# working.net
KiCad netlist of a schematic drawn in EAGLE
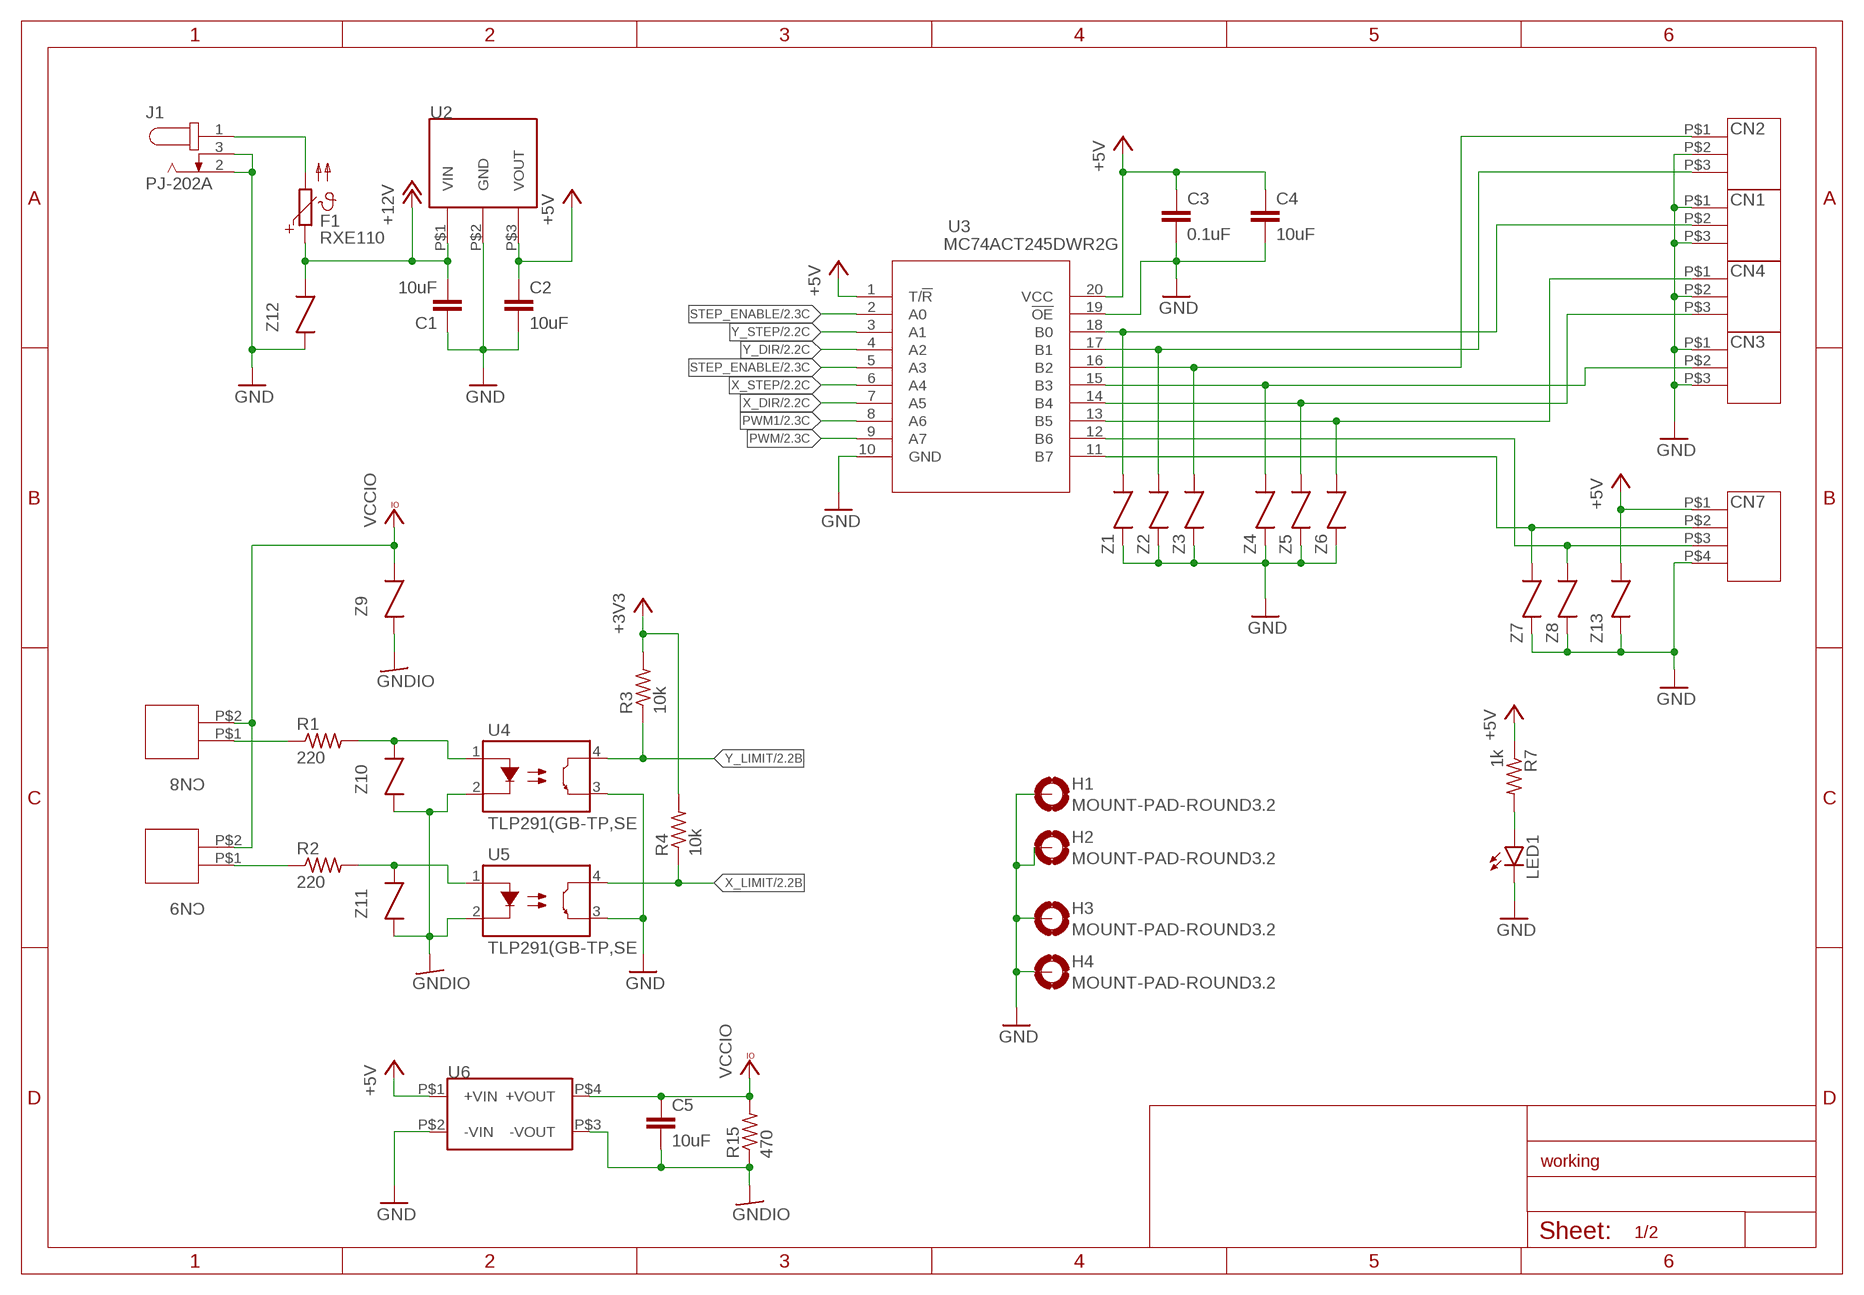
[diagram p0: schematic, sheet 1]
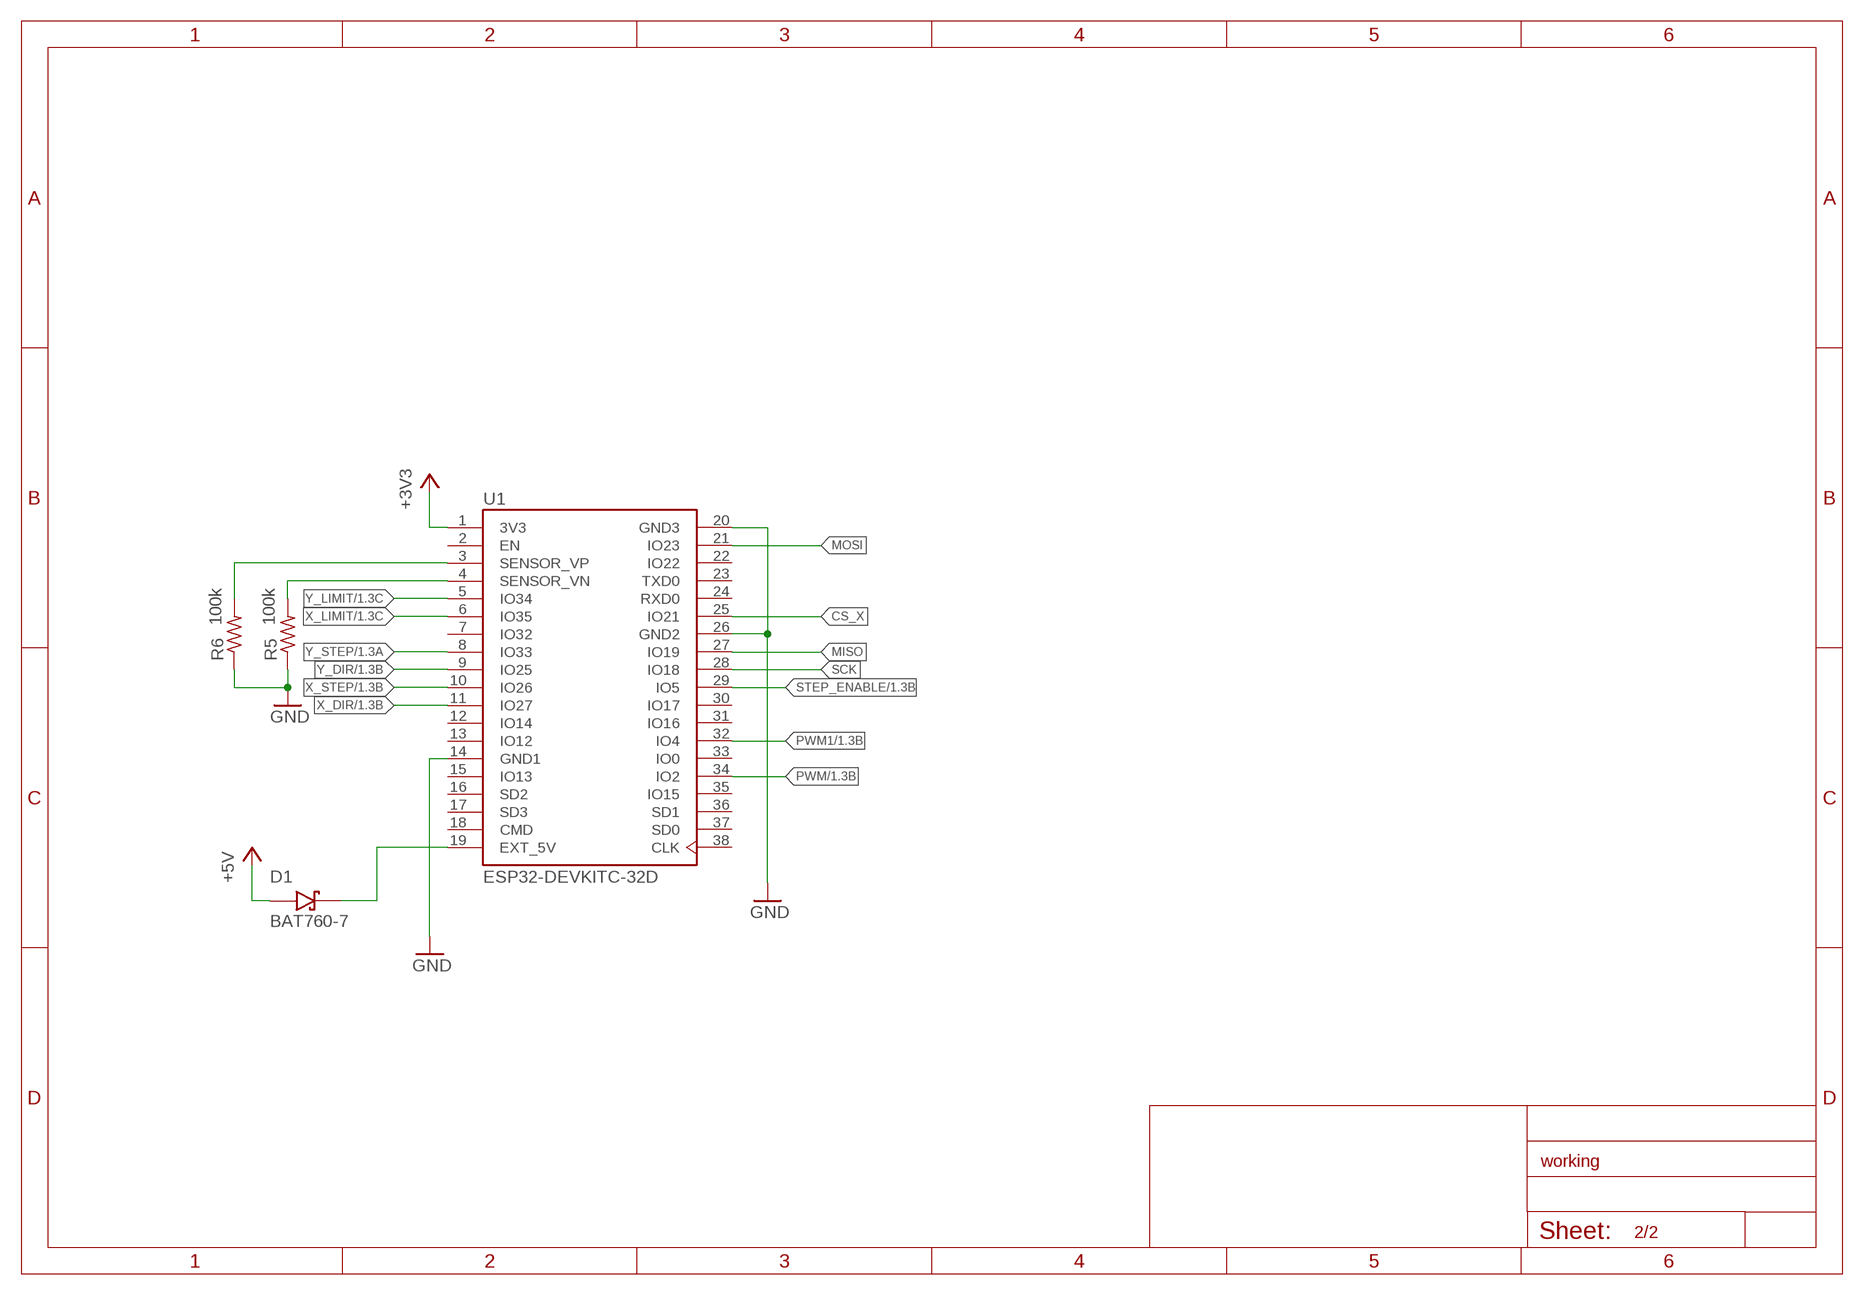
[diagram p1: schematic, sheet 2]

(export (version "E")
  (design (tool "Eeschema 10.0.6"))
  (components
    (comp (ref "C1")
      (value "10uF")
      (footprint "eagle-import:C0805")
      (libsource (lib "eagle-import") (part "C-EUC0805"))
    )
    (comp (ref "C2")
      (value "10uF")
      (footprint "eagle-import:C0805")
      (libsource (lib "eagle-import") (part "C-EUC0805"))
    )
    (comp (ref "C3")
      (value "0.1uF")
      (footprint "eagle-import:C0603")
      (libsource (lib "eagle-import") (part "C-EUC0603"))
    )
    (comp (ref "C4")
      (value "10uF")
      (footprint "eagle-import:C0805")
      (libsource (lib "eagle-import") (part "C-EUC0805"))
    )
    (comp (ref "C5")
      (value "10uF")
      (footprint "eagle-import:C0805")
      (libsource (lib "eagle-import") (part "C-EUC0805"))
    )
    (comp (ref "CN1")
      (value "ETB43034G000Z")
      (footprint "eagle-import:ETB43034G000Z")
      (libsource (lib "eagle-import") (part "ETB43034G000Z"))
    )
    (comp (ref "CN2")
      (value "ETB43034G000Z")
      (footprint "eagle-import:ETB43034G000Z")
      (libsource (lib "eagle-import") (part "ETB43034G000Z"))
    )
    (comp (ref "CN3")
      (value "ETB43034G000Z")
      (footprint "eagle-import:ETB43034G000Z")
      (libsource (lib "eagle-import") (part "ETB43034G000Z"))
    )
    (comp (ref "CN4")
      (value "ETB43034G000Z")
      (footprint "eagle-import:ETB43034G000Z")
      (libsource (lib "eagle-import") (part "ETB43034G000Z"))
    )
    (comp (ref "CN7")
      (value "ETB43044G000Z")
      (footprint "eagle-import:ETB43044G000Z")
      (libsource (lib "eagle-import") (part "ETB43044G000Z"))
    )
    (comp (ref "CN8")
      (value "ETB43024G000Z")
      (footprint "eagle-import:ETB43024G000Z")
      (libsource (lib "eagle-import") (part "ETB43024G000Z"))
    )
    (comp (ref "CN9")
      (value "ETB43024G000Z")
      (footprint "eagle-import:ETB43024G000Z")
      (libsource (lib "eagle-import") (part "ETB43024G000Z"))
    )
    (comp (ref "F1")
      (value "RXE110")
      (footprint "eagle-import:RXE110")
      (libsource (lib "eagle-import") (part "RXE110"))
    )
    (comp (ref "H1")
      (value "MOUNT-PAD-ROUND3.2")
      (footprint "eagle-import:3,2-PAD")
      (libsource (lib "eagle-import") (part "MOUNT-PAD-ROUND3.2"))
    )
    (comp (ref "H2")
      (value "MOUNT-PAD-ROUND3.2")
      (footprint "eagle-import:3,2-PAD")
      (libsource (lib "eagle-import") (part "MOUNT-PAD-ROUND3.2"))
    )
    (comp (ref "H3")
      (value "MOUNT-PAD-ROUND3.2")
      (footprint "eagle-import:3,2-PAD")
      (libsource (lib "eagle-import") (part "MOUNT-PAD-ROUND3.2"))
    )
    (comp (ref "H4")
      (value "MOUNT-PAD-ROUND3.2")
      (footprint "eagle-import:3,2-PAD")
      (libsource (lib "eagle-import") (part "MOUNT-PAD-ROUND3.2"))
    )
    (comp (ref "J1")
      (value "PJ-202A")
      (footprint "eagle-import:CUI_PJ-202A")
      (fields (field (name "MF") "CUI Devices"))
      (libsource (lib "eagle-import") (part "PJ-202A"))
    )
    (comp (ref "LED1")
      (value "LED3MM")
      (footprint "eagle-import:LED3MM")
      (libsource (lib "eagle-import") (part "LED3MM"))
    )
    (comp (ref "R1")
      (value "220")
      (footprint "eagle-import:R0603")
      (libsource (lib "eagle-import") (part "R-US_R0603"))
    )
    (comp (ref "R2")
      (value "220")
      (footprint "eagle-import:R0603")
      (libsource (lib "eagle-import") (part "R-US_R0603"))
    )
    (comp (ref "R3")
      (value "10k")
      (footprint "eagle-import:R0603")
      (libsource (lib "eagle-import") (part "R-US_R0603"))
    )
    (comp (ref "R4")
      (value "10k")
      (footprint "eagle-import:R0603")
      (libsource (lib "eagle-import") (part "R-US_R0603"))
    )
    (comp (ref "R7")
      (value "1k")
      (footprint "eagle-import:R0603")
      (libsource (lib "eagle-import") (part "R-US_R0603"))
    )
    (comp (ref "R15")
      (value "470")
      (footprint "eagle-import:R0603")
      (libsource (lib "eagle-import") (part "R-US_R0603"))
    )
    (comp (ref "U2")
      (value "BP5293-50BP5293_SIDE")
      (footprint "eagle-import:BP5293_SIDE")
      (libsource (lib "eagle-import") (part "BP5293-50BP5293_SIDE"))
    )
    (comp (ref "U3")
      (value "MC74ACT245DWR2G")
      (footprint "eagle-import:SOIC-20WB_ONS")
      (fields (field (name "COPYRIGHT") "Copyright (C) 2022 Ultra Librarian. All rights reserved."))
      (libsource (lib "eagle-import") (part "MC74ACT245DWR2G"))
    )
    (comp (ref "U4")
      (value "TLP291(GB-TP,SE")
      (footprint "eagle-import:SOIC127P700X220-4N")
      (fields (field (name "MF") "Toshiba Semiconductor"))
      (libsource (lib "eagle-import") (part "TLP291(GB-TP,SE"))
    )
    (comp (ref "U5")
      (value "TLP291(GB-TP,SE")
      (footprint "eagle-import:SOIC127P700X220-4N")
      (fields (field (name "MF") "Toshiba Semiconductor"))
      (libsource (lib "eagle-import") (part "TLP291(GB-TP,SE"))
    )
    (comp (ref "U6")
      (value "MAU102")
      (footprint "eagle-import:MAU100_SINGLE")
      (libsource (lib "eagle-import") (part "MAU102"))
    )
    (comp (ref "Z1")
      (value "MLVC06V012C210")
      (footprint "eagle-import:0603")
      (libsource (lib "eagle-import") (part "MLVC06V012C210"))
    )
    (comp (ref "Z2")
      (value "MLVC06V012C210")
      (footprint "eagle-import:0603")
      (libsource (lib "eagle-import") (part "MLVC06V012C210"))
    )
    (comp (ref "Z3")
      (value "MLVC06V012C210")
      (footprint "eagle-import:0603")
      (libsource (lib "eagle-import") (part "MLVC06V012C210"))
    )
    (comp (ref "Z4")
      (value "MLVC06V012C210")
      (footprint "eagle-import:0603")
      (libsource (lib "eagle-import") (part "MLVC06V012C210"))
    )
    (comp (ref "Z5")
      (value "MLVC06V012C210")
      (footprint "eagle-import:0603")
      (libsource (lib "eagle-import") (part "MLVC06V012C210"))
    )
    (comp (ref "Z6")
      (value "MLVC06V012C210")
      (footprint "eagle-import:0603")
      (libsource (lib "eagle-import") (part "MLVC06V012C210"))
    )
    (comp (ref "Z7")
      (value "MLVC06V012C210")
      (footprint "eagle-import:0603")
      (libsource (lib "eagle-import") (part "MLVC06V012C210"))
    )
    (comp (ref "Z8")
      (value "MLVC06V012C210")
      (footprint "eagle-import:0603")
      (libsource (lib "eagle-import") (part "MLVC06V012C210"))
    )
    (comp (ref "Z9")
      (value "MLVC06V012C210")
      (footprint "eagle-import:0603")
      (libsource (lib "eagle-import") (part "MLVC06V012C210"))
    )
    (comp (ref "Z10")
      (value "MLVC06V012C210")
      (footprint "eagle-import:0603")
      (libsource (lib "eagle-import") (part "MLVC06V012C210"))
    )
    (comp (ref "Z11")
      (value "MLVC06V012C210")
      (footprint "eagle-import:0603")
      (libsource (lib "eagle-import") (part "MLVC06V012C210"))
    )
    (comp (ref "Z12")
      (value "MLVC06V026C120")
      (footprint "eagle-import:0603")
      (libsource (lib "eagle-import") (part "MLVC06V026C120"))
    )
    (comp (ref "Z13")
      (value "MLVC06V012C210")
      (footprint "eagle-import:0603")
      (libsource (lib "eagle-import") (part "MLVC06V012C210"))
    )
    (comp (ref "D1")
      (value "BAT760-7")
      (footprint "eagle-import:SOD2513X120N")
      (fields (field (name "MF") "Diodes Inc."))
      (libsource (lib "eagle-import") (part "BAT760-7"))
    )
    (comp (ref "R5")
      (value "100k")
      (footprint "eagle-import:R0603")
      (libsource (lib "eagle-import") (part "R-US_R0603"))
    )
    (comp (ref "R6")
      (value "100k")
      (footprint "eagle-import:R0603")
      (libsource (lib "eagle-import") (part "R-US_R0603"))
    )
    (comp (ref "U1")
      (value "ESP32-DEVKITC-32D")
      (footprint "eagle-import:MODULE_ESP32-DEVKITC-32D")
      (fields (field (name "MF") "Espressif Systems"))
      (libsource (lib "eagle-import") (part "ESP32-DEVKITC-32D"))
    )
  )
  (nets
    (net (code "1") (name "+3V3") (class "Default")
      (node (ref "R3") (pin "2") (pinfunction "2_2") (pintype "passive"))
      (node (ref "R4") (pin "2") (pinfunction "2_2") (pintype "passive"))
      (node (ref "U1") (pin "1") (pinfunction "3V3_1") (pintype "power_in"))
    )
    (net (code "2") (name "+5V") (class "Default")
      (node (ref "C2") (pin "2") (pinfunction "2_2") (pintype "passive"))
      (node (ref "C3") (pin "1") (pinfunction "1_1") (pintype "passive"))
      (node (ref "C4") (pin "2") (pinfunction "2_2") (pintype "passive"))
      (node (ref "CN7") (pin "P$1") (pinfunction "1_P$1") (pintype "passive"))
      (node (ref "D1") (pin "A") (pinfunction "A_A") (pintype "passive"))
      (node (ref "R7") (pin "1") (pinfunction "1_1") (pintype "passive"))
      (node (ref "U2") (pin "P$3") (pinfunction "VOUT_P$3") (pintype "bidirectional"))
      (node (ref "U3") (pin "1") (pinfunction "T/~{R}_1") (pintype "input"))
      (node (ref "U3") (pin "20") (pinfunction "VCC_20") (pintype "power_in"))
      (node (ref "U6") (pin "P$1") (pinfunction "+VIN_P$1") (pintype "bidirectional"))
      (node (ref "Z13") (pin "1") (pinfunction "1_1") (pintype "passive"))
    )
    (net (code "3") (name "+12V") (class "Default")
      (node (ref "C1") (pin "2") (pinfunction "2_2") (pintype "passive"))
      (node (ref "F1") (pin "P$1") (pinfunction "1_P$1") (pintype "passive"))
      (node (ref "U2") (pin "P$1") (pinfunction "VIN_P$1") (pintype "bidirectional"))
      (node (ref "Z12") (pin "1") (pinfunction "1_1") (pintype "passive"))
    )
    (net (code "4") (name "CS_X") (class "Default")
      (node (ref "U1") (pin "25") (pinfunction "IO21_25") (pintype "bidirectional"))
    )
    (net (code "5") (name "GND") (class "Default")
      (node (ref "C1") (pin "1") (pinfunction "1_1") (pintype "passive"))
      (node (ref "C2") (pin "1") (pinfunction "1_1") (pintype "passive"))
      (node (ref "C3") (pin "2") (pinfunction "2_2") (pintype "passive"))
      (node (ref "C4") (pin "1") (pinfunction "1_1") (pintype "passive"))
      (node (ref "CN1") (pin "P$1") (pinfunction "1_P$1") (pintype "passive"))
      (node (ref "CN1") (pin "P$3") (pinfunction "3_P$3") (pintype "passive"))
      (node (ref "CN2") (pin "P$2") (pinfunction "2_P$2") (pintype "passive"))
      (node (ref "CN3") (pin "P$1") (pinfunction "1_P$1") (pintype "passive"))
      (node (ref "CN3") (pin "P$3") (pinfunction "3_P$3") (pintype "passive"))
      (node (ref "CN4") (pin "P$2") (pinfunction "2_P$2") (pintype "passive"))
      (node (ref "CN7") (pin "P$4") (pinfunction "4_P$4") (pintype "passive"))
      (node (ref "H1") (pin "B3,2") (pinfunction "MOUNT_B3,2") (pintype "passive"))
      (node (ref "H2") (pin "B3,2") (pinfunction "MOUNT_B3,2") (pintype "passive"))
      (node (ref "H3") (pin "B3,2") (pinfunction "MOUNT_B3,2") (pintype "passive"))
      (node (ref "H4") (pin "B3,2") (pinfunction "MOUNT_B3,2") (pintype "passive"))
      (node (ref "J1") (pin "2") (pinfunction "2_2") (pintype "passive"))
      (node (ref "J1") (pin "3") (pinfunction "3_3") (pintype "passive"))
      (node (ref "LED1") (pin "K") (pinfunction "C_K") (pintype "passive"))
      (node (ref "R5") (pin "1") (pinfunction "1_1") (pintype "passive"))
      (node (ref "R6") (pin "1") (pinfunction "1_1") (pintype "passive"))
      (node (ref "U1") (pin "14") (pinfunction "GND1_14") (pintype "power_in"))
      (node (ref "U1") (pin "20") (pinfunction "GND3_20") (pintype "power_in"))
      (node (ref "U1") (pin "26") (pinfunction "GND2_26") (pintype "power_in"))
      (node (ref "U2") (pin "P$2") (pinfunction "GND_P$2") (pintype "bidirectional"))
      (node (ref "U3") (pin "10") (pinfunction "GND_10") (pintype "power_in"))
      (node (ref "U3") (pin "19") (pinfunction "~{OE}_19") (pintype "bidirectional"))
      (node (ref "U4") (pin "3") (pinfunction "EMIT_3") (pintype "passive"))
      (node (ref "U5") (pin "3") (pinfunction "EMIT_3") (pintype "passive"))
      (node (ref "U6") (pin "P$2") (pinfunction "-VIN_P$2") (pintype "bidirectional"))
      (node (ref "Z1") (pin "2") (pinfunction "2_2") (pintype "passive"))
      (node (ref "Z12") (pin "2") (pinfunction "2_2") (pintype "passive"))
      (node (ref "Z13") (pin "2") (pinfunction "2_2") (pintype "passive"))
      (node (ref "Z2") (pin "2") (pinfunction "2_2") (pintype "passive"))
      (node (ref "Z3") (pin "2") (pinfunction "2_2") (pintype "passive"))
      (node (ref "Z4") (pin "2") (pinfunction "2_2") (pintype "passive"))
      (node (ref "Z5") (pin "2") (pinfunction "2_2") (pintype "passive"))
      (node (ref "Z6") (pin "2") (pinfunction "2_2") (pintype "passive"))
      (node (ref "Z7") (pin "2") (pinfunction "2_2") (pintype "passive"))
      (node (ref "Z8") (pin "2") (pinfunction "2_2") (pintype "passive"))
    )
    (net (code "6") (name "GNDIO") (class "Default")
      (node (ref "C5") (pin "1") (pinfunction "1_1") (pintype "passive"))
      (node (ref "R15") (pin "1") (pinfunction "1_1") (pintype "passive"))
      (node (ref "U4") (pin "2") (pinfunction "C_2") (pintype "passive"))
      (node (ref "U5") (pin "2") (pinfunction "C_2") (pintype "passive"))
      (node (ref "U6") (pin "P$3") (pinfunction "-VOUT_P$3") (pintype "bidirectional"))
      (node (ref "Z10") (pin "2") (pinfunction "2_2") (pintype "passive"))
      (node (ref "Z11") (pin "2") (pinfunction "2_2") (pintype "passive"))
      (node (ref "Z9") (pin "2") (pinfunction "2_2") (pintype "passive"))
    )
    (net (code "7") (name "MISO") (class "Default")
      (node (ref "U1") (pin "27") (pinfunction "IO19_27") (pintype "bidirectional"))
    )
    (net (code "8") (name "MOSI") (class "Default")
      (node (ref "U1") (pin "21") (pinfunction "IO23_21") (pintype "bidirectional"))
    )
    (net (code "9") (name "Net-(CN1-2)") (class "Default")
      (node (ref "CN1") (pin "P$2") (pinfunction "2_P$2") (pintype "passive"))
      (node (ref "U3") (pin "18") (pinfunction "B0_18") (pintype "bidirectional"))
      (node (ref "Z1") (pin "1") (pinfunction "1_1") (pintype "passive"))
    )
    (net (code "10") (name "Net-(CN2-1)") (class "Default")
      (node (ref "CN2") (pin "P$1") (pinfunction "1_P$1") (pintype "passive"))
      (node (ref "U3") (pin "16") (pinfunction "B2_16") (pintype "bidirectional"))
      (node (ref "Z3") (pin "1") (pinfunction "1_1") (pintype "passive"))
    )
    (net (code "11") (name "Net-(CN2-3)") (class "Default")
      (node (ref "CN2") (pin "P$3") (pinfunction "3_P$3") (pintype "passive"))
      (node (ref "U3") (pin "17") (pinfunction "B1_17") (pintype "bidirectional"))
      (node (ref "Z2") (pin "1") (pinfunction "1_1") (pintype "passive"))
    )
    (net (code "12") (name "Net-(CN3-2)") (class "Default")
      (node (ref "CN3") (pin "P$2") (pinfunction "2_P$2") (pintype "passive"))
      (node (ref "U3") (pin "15") (pinfunction "B3_15") (pintype "bidirectional"))
      (node (ref "Z4") (pin "1") (pinfunction "1_1") (pintype "passive"))
    )
    (net (code "13") (name "Net-(CN4-1)") (class "Default")
      (node (ref "CN4") (pin "P$1") (pinfunction "1_P$1") (pintype "passive"))
      (node (ref "U3") (pin "13") (pinfunction "B5_13") (pintype "bidirectional"))
      (node (ref "Z6") (pin "1") (pinfunction "1_1") (pintype "passive"))
    )
    (net (code "14") (name "Net-(CN4-3)") (class "Default")
      (node (ref "CN4") (pin "P$3") (pinfunction "3_P$3") (pintype "passive"))
      (node (ref "U3") (pin "14") (pinfunction "B4_14") (pintype "bidirectional"))
      (node (ref "Z5") (pin "1") (pinfunction "1_1") (pintype "passive"))
    )
    (net (code "15") (name "Net-(CN7-2)") (class "Default")
      (node (ref "CN7") (pin "P$2") (pinfunction "2_P$2") (pintype "passive"))
      (node (ref "U3") (pin "11") (pinfunction "B7_11") (pintype "bidirectional"))
      (node (ref "Z7") (pin "1") (pinfunction "1_1") (pintype "passive"))
    )
    (net (code "16") (name "Net-(CN7-3)") (class "Default")
      (node (ref "CN7") (pin "P$3") (pinfunction "3_P$3") (pintype "passive"))
      (node (ref "U3") (pin "12") (pinfunction "B6_12") (pintype "bidirectional"))
      (node (ref "Z8") (pin "1") (pinfunction "1_1") (pintype "passive"))
    )
    (net (code "17") (name "Net-(CN8-1)") (class "Default")
      (node (ref "CN8") (pin "P$1") (pinfunction "1_P$1") (pintype "passive"))
      (node (ref "R1") (pin "1") (pinfunction "1_1") (pintype "passive"))
    )
    (net (code "18") (name "Net-(CN9-1)") (class "Default")
      (node (ref "CN9") (pin "P$1") (pinfunction "1_P$1") (pintype "passive"))
      (node (ref "R2") (pin "1") (pinfunction "1_1") (pintype "passive"))
    )
    (net (code "19") (name "Net-(D1-K)") (class "Default")
      (node (ref "D1") (pin "C") (pinfunction "K_C") (pintype "passive"))
      (node (ref "U1") (pin "19") (pinfunction "EXT_5V_19") (pintype "power_in"))
    )
    (net (code "20") (name "Net-(F1-2)") (class "Default")
      (node (ref "F1") (pin "P$2") (pinfunction "2_P$2") (pintype "passive"))
      (node (ref "J1") (pin "1") (pinfunction "1_1") (pintype "passive"))
    )
    (net (code "21") (name "Net-(LED1-PadA)") (class "Default")
      (node (ref "LED1") (pin "A") (pinfunction "A_A") (pintype "passive"))
      (node (ref "R7") (pin "2") (pinfunction "2_2") (pintype "passive"))
    )
    (net (code "22") (name "Net-(U1-SENSOR_VN)") (class "Default")
      (node (ref "R5") (pin "2") (pinfunction "2_2") (pintype "passive"))
      (node (ref "U1") (pin "4") (pinfunction "SENSOR_VN_4") (pintype "input"))
    )
    (net (code "23") (name "Net-(U1-SENSOR_VP)") (class "Default")
      (node (ref "R6") (pin "2") (pinfunction "2_2") (pintype "passive"))
      (node (ref "U1") (pin "3") (pinfunction "SENSOR_VP_3") (pintype "input"))
    )
    (net (code "24") (name "Net-(U4-A)") (class "Default")
      (node (ref "R1") (pin "2") (pinfunction "2_2") (pintype "passive"))
      (node (ref "U4") (pin "1") (pinfunction "A_1") (pintype "passive"))
      (node (ref "Z10") (pin "1") (pinfunction "1_1") (pintype "passive"))
    )
    (net (code "25") (name "Net-(U5-A)") (class "Default")
      (node (ref "R2") (pin "2") (pinfunction "2_2") (pintype "passive"))
      (node (ref "U5") (pin "1") (pinfunction "A_1") (pintype "passive"))
      (node (ref "Z11") (pin "1") (pinfunction "1_1") (pintype "passive"))
    )
    (net (code "26") (name "PWM") (class "Default")
      (node (ref "U1") (pin "34") (pinfunction "IO2_34") (pintype "bidirectional"))
      (node (ref "U3") (pin "9") (pinfunction "A7_9") (pintype "bidirectional"))
    )
    (net (code "27") (name "PWM1") (class "Default")
      (node (ref "U1") (pin "32") (pinfunction "IO4_32") (pintype "bidirectional"))
      (node (ref "U3") (pin "8") (pinfunction "A6_8") (pintype "bidirectional"))
    )
    (net (code "28") (name "SCK") (class "Default")
      (node (ref "U1") (pin "28") (pinfunction "IO18_28") (pintype "bidirectional"))
    )
    (net (code "29") (name "STEP_ENABLE") (class "Default")
      (node (ref "U1") (pin "29") (pinfunction "IO5_29") (pintype "bidirectional"))
      (node (ref "U3") (pin "2") (pinfunction "A0_2") (pintype "bidirectional"))
      (node (ref "U3") (pin "5") (pinfunction "A3_5") (pintype "bidirectional"))
    )
    (net (code "30") (name "VCCIO") (class "Default")
      (node (ref "C5") (pin "2") (pinfunction "2_2") (pintype "passive"))
      (node (ref "CN8") (pin "P$2") (pinfunction "2_P$2") (pintype "passive"))
      (node (ref "CN9") (pin "P$2") (pinfunction "2_P$2") (pintype "passive"))
      (node (ref "R15") (pin "2") (pinfunction "2_2") (pintype "passive"))
      (node (ref "U6") (pin "P$4") (pinfunction "+VOUT_P$4") (pintype "bidirectional"))
      (node (ref "Z9") (pin "1") (pinfunction "1_1") (pintype "passive"))
    )
    (net (code "31") (name "X_DIR") (class "Default")
      (node (ref "U1") (pin "11") (pinfunction "IO27_11") (pintype "bidirectional"))
      (node (ref "U3") (pin "7") (pinfunction "A5_7") (pintype "bidirectional"))
    )
    (net (code "32") (name "X_LIMIT") (class "Default")
      (node (ref "R4") (pin "1") (pinfunction "1_1") (pintype "passive"))
      (node (ref "U1") (pin "6") (pinfunction "IO35_6") (pintype "bidirectional"))
      (node (ref "U5") (pin "4") (pinfunction "COL_4") (pintype "passive"))
    )
    (net (code "33") (name "X_STEP") (class "Default")
      (node (ref "U1") (pin "10") (pinfunction "IO26_10") (pintype "bidirectional"))
      (node (ref "U3") (pin "6") (pinfunction "A4_6") (pintype "bidirectional"))
    )
    (net (code "34") (name "Y_DIR") (class "Default")
      (node (ref "U1") (pin "9") (pinfunction "IO25_9") (pintype "bidirectional"))
      (node (ref "U3") (pin "4") (pinfunction "A2_4") (pintype "bidirectional"))
    )
    (net (code "35") (name "Y_LIMIT") (class "Default")
      (node (ref "R3") (pin "1") (pinfunction "1_1") (pintype "passive"))
      (node (ref "U1") (pin "5") (pinfunction "IO34_5") (pintype "bidirectional"))
      (node (ref "U4") (pin "4") (pinfunction "COL_4") (pintype "passive"))
    )
    (net (code "36") (name "Y_STEP") (class "Default")
      (node (ref "U1") (pin "8") (pinfunction "IO33_8") (pintype "bidirectional"))
      (node (ref "U3") (pin "3") (pinfunction "A1_3") (pintype "bidirectional"))
    )
    (net (code "37") (name "unconnected-(U1-CLK-Pad38)") (class "Default")
      (node (ref "U1") (pin "38") (pinfunction "CLK_38") (pintype "input"))
    )
    (net (code "38") (name "unconnected-(U1-CMD-Pad18)") (class "Default")
      (node (ref "U1") (pin "18") (pinfunction "CMD_18") (pintype "bidirectional"))
    )
    (net (code "39") (name "unconnected-(U1-EN-Pad2)") (class "Default")
      (node (ref "U1") (pin "2") (pinfunction "EN_2") (pintype "input"))
    )
    (net (code "40") (name "unconnected-(U1-IO0-Pad33)") (class "Default")
      (node (ref "U1") (pin "33") (pinfunction "IO0_33") (pintype "bidirectional"))
    )
    (net (code "41") (name "unconnected-(U1-IO12-Pad13)") (class "Default")
      (node (ref "U1") (pin "13") (pinfunction "IO12_13") (pintype "bidirectional"))
    )
    (net (code "42") (name "unconnected-(U1-IO13-Pad15)") (class "Default")
      (node (ref "U1") (pin "15") (pinfunction "IO13_15") (pintype "bidirectional"))
    )
    (net (code "43") (name "unconnected-(U1-IO14-Pad12)") (class "Default")
      (node (ref "U1") (pin "12") (pinfunction "IO14_12") (pintype "bidirectional"))
    )
    (net (code "44") (name "unconnected-(U1-IO15-Pad35)") (class "Default")
      (node (ref "U1") (pin "35") (pinfunction "IO15_35") (pintype "bidirectional"))
    )
    (net (code "45") (name "unconnected-(U1-IO16-Pad31)") (class "Default")
      (node (ref "U1") (pin "31") (pinfunction "IO16_31") (pintype "bidirectional"))
    )
    (net (code "46") (name "unconnected-(U1-IO17-Pad30)") (class "Default")
      (node (ref "U1") (pin "30") (pinfunction "IO17_30") (pintype "bidirectional"))
    )
    (net (code "47") (name "unconnected-(U1-IO22-Pad22)") (class "Default")
      (node (ref "U1") (pin "22") (pinfunction "IO22_22") (pintype "bidirectional"))
    )
    (net (code "48") (name "unconnected-(U1-IO32-Pad7)") (class "Default")
      (node (ref "U1") (pin "7") (pinfunction "IO32_7") (pintype "bidirectional"))
    )
    (net (code "49") (name "unconnected-(U1-RXD0-Pad24)") (class "Default")
      (node (ref "U1") (pin "24") (pinfunction "RXD0_24") (pintype "input"))
    )
    (net (code "50") (name "unconnected-(U1-SD0-Pad37)") (class "Default")
      (node (ref "U1") (pin "37") (pinfunction "SD0_37") (pintype "bidirectional"))
    )
    (net (code "51") (name "unconnected-(U1-SD1-Pad36)") (class "Default")
      (node (ref "U1") (pin "36") (pinfunction "SD1_36") (pintype "bidirectional"))
    )
    (net (code "52") (name "unconnected-(U1-SD2-Pad16)") (class "Default")
      (node (ref "U1") (pin "16") (pinfunction "SD2_16") (pintype "bidirectional"))
    )
    (net (code "53") (name "unconnected-(U1-SD3-Pad17)") (class "Default")
      (node (ref "U1") (pin "17") (pinfunction "SD3_17") (pintype "bidirectional"))
    )
    (net (code "54") (name "unconnected-(U1-TXD0-Pad23)") (class "Default")
      (node (ref "U1") (pin "23") (pinfunction "TXD0_23") (pintype "output"))
    )
  )
)
